# Gateway.net
KiCad netlist of a schematic drawn in Altium Designer
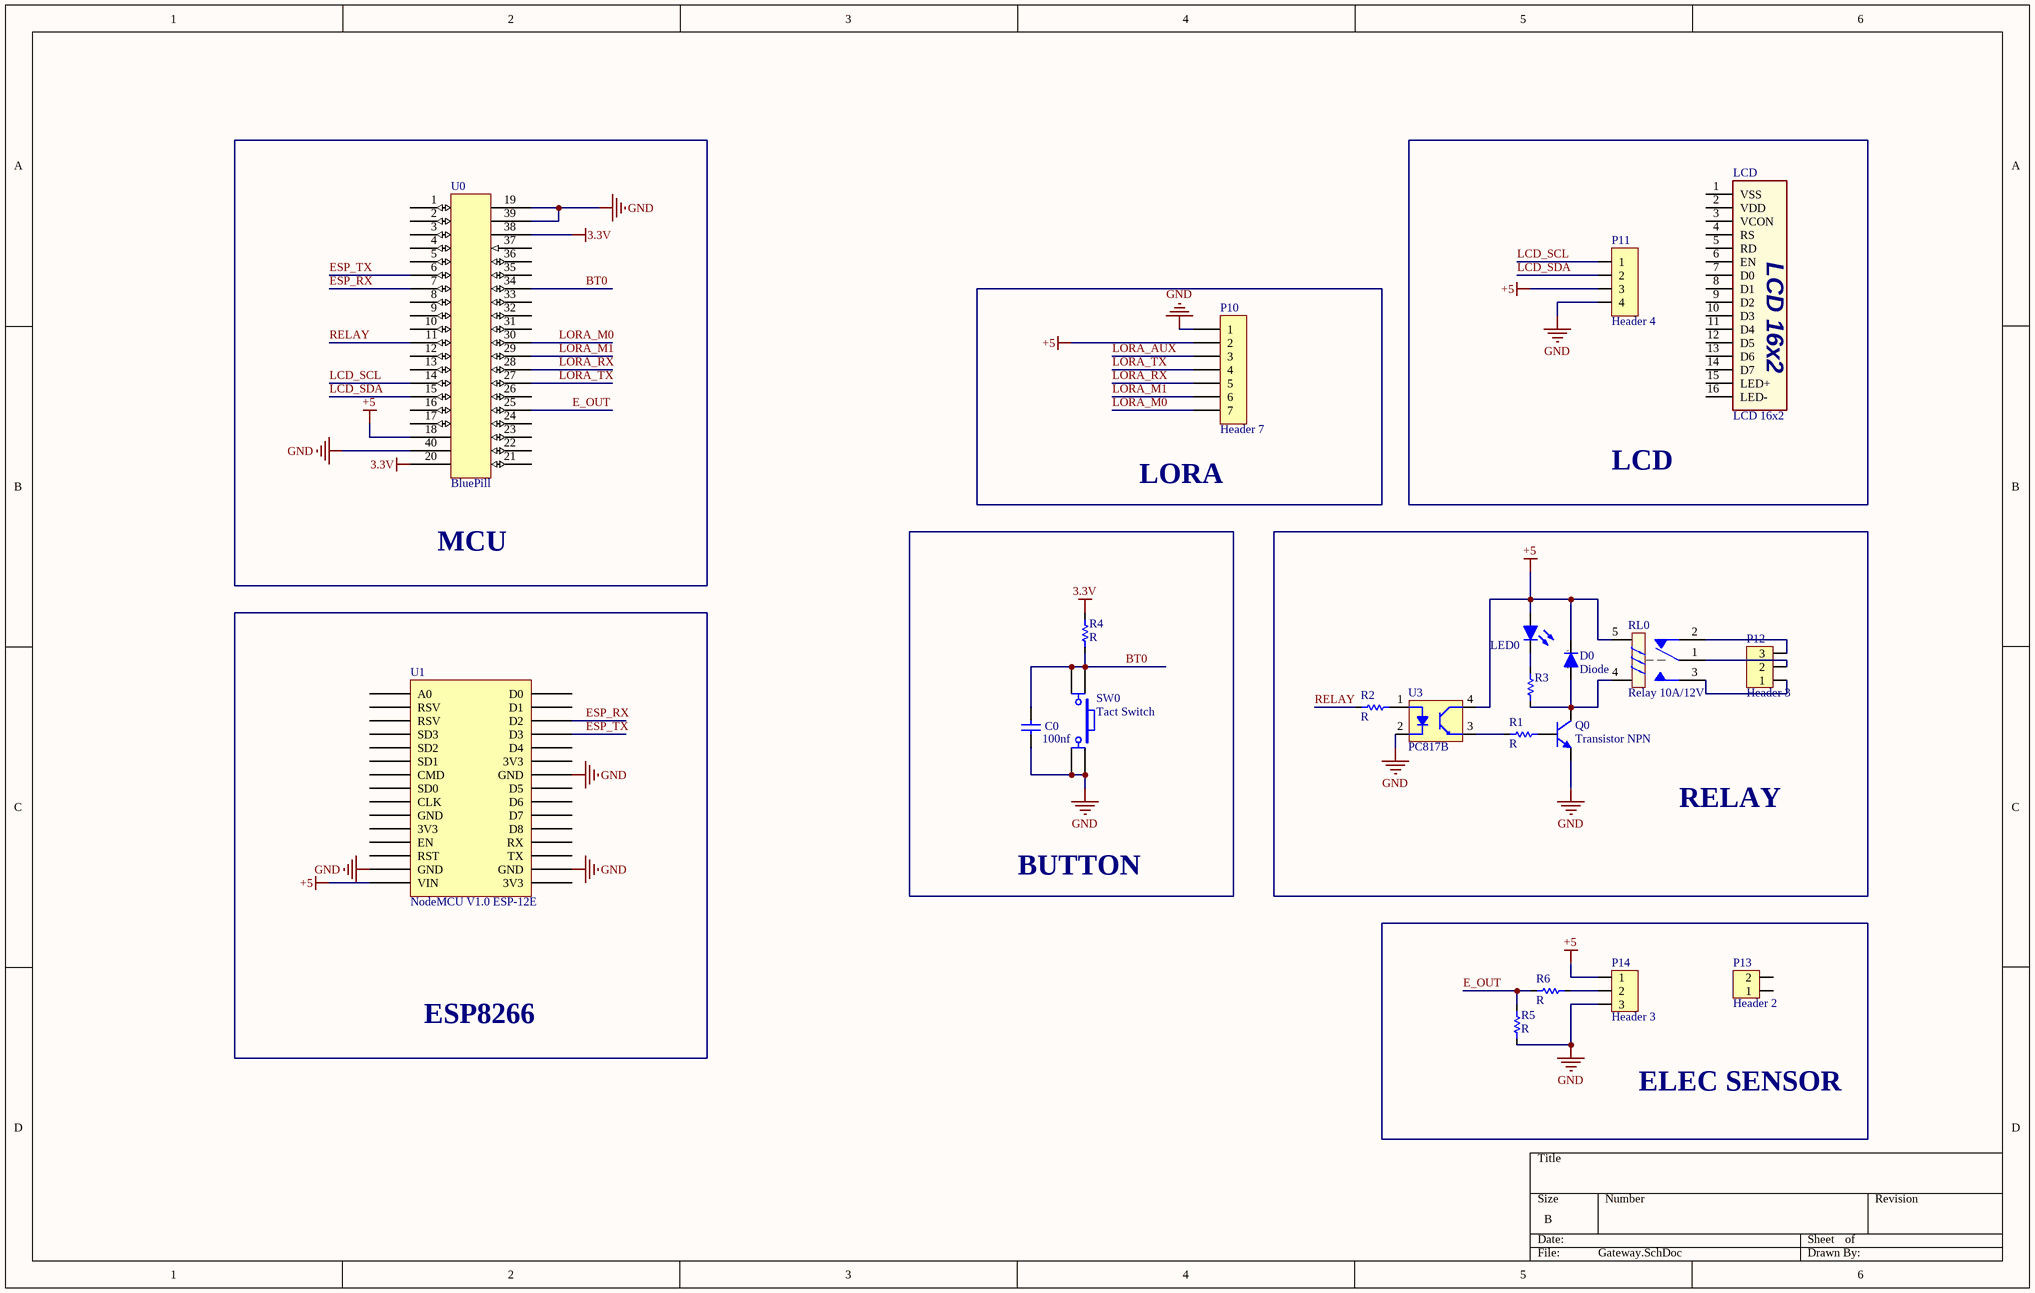
[diagram p0: Gateway.SchDoc]

(export (version "E")
  (design (tool "Eeschema 10.0.6"))
  (components
    (comp (ref "C0")
      (value "100nf")
      (footprint "C 0805 (2012)")
      (description "Capacitor non-pol")
      (libsource (lib "BKIT4U_LIB_NEW") (part "Capacitor NP"))
    )
    (comp (ref "D0")
      (value "Diode")
      (footprint "SOD-80")
      (description "Default Diode")
      (fields (field (name "PUBLISHER") "Altium Limited"))
      (libsource (lib "BKIT4U_LIB_NEW") (part "Diode"))
    )
    (comp (ref "LCD")
      (value "LCD 16x2")
      (footprint "LCD 16x2")
      (description "Character LCD 16x2")
      (libsource (lib "BKIT4U_LIB_NEW") (part "LCD 16x2"))
    )
    (comp (ref "LED0")
      (value "Led")
      (footprint "LED 3MM")
      (description "Typical LED")
      (libsource (lib "BKIT4U_LIB_NEW") (part "Led"))
    )
    (comp (ref "P10")
      (value "Header 7")
      (footprint "Header 7")
      (description "Header, 7-Pin")
      (fields (field (name "PUBLISHER") "Altium Limited"))
      (libsource (lib "BKIT4U_LIB_NEW") (part "Header 7"))
    )
    (comp (ref "P11")
      (value "Header 4")
      (footprint "XH2.54-4P-RA")
      (description "Header, 4-Pin")
      (libsource (lib "BKIT4U_LIB_NEW") (part "Header 4"))
    )
    (comp (ref "P12")
      (value "Header 3")
      (footprint "SH152-5.08-3P")
      (description "Header, 3-Pin")
      (libsource (lib "") (part "Header 3_1"))
    )
    (comp (ref "P13")
      (value "Header 2")
      (footprint "HDR Domino 2 - 5MM")
      (description "Header, 2-Pin")
      (fields (field (name "PUBLISHER") "Altium Limited"))
      (libsource (lib "BKIT4U_LIB_NEW") (part "Header 2"))
    )
    (comp (ref "P14")
      (value "Header 3")
      (footprint "Header 3")
      (description "Header, 3-Pin")
      (libsource (lib "BKIT4U_LIB_NEW") (part "Header 3"))
    )
    (comp (ref "Q0")
      (value "Transistor NPN")
      (footprint "SOT-23")
      (description "NPN Bipolar Transistor")
      (libsource (lib "BKIT4U_LIB_NEW") (part "Transistor NPN"))
    )
    (comp (ref "R1")
      (value "R")
      (footprint "R 0805 (2012)")
      (description "Resistor")
      (fields (field (name "PUBLISHER") "Altium Limited"))
      (libsource (lib "BKIT4U_LIB_NEW") (part "Resistor"))
    )
    (comp (ref "R2")
      (value "R")
      (footprint "R 0805 (2012)")
      (description "Resistor")
      (fields (field (name "PUBLISHER") "Altium Limited"))
      (libsource (lib "BKIT4U_LIB_NEW") (part "Resistor"))
    )
    (comp (ref "R3")
      (value "R0")
      (footprint "R 0805 (2012)")
      (description "Resistor")
      (fields (field (name "PUBLISHER") "Altium Limited"))
      (libsource (lib "BKIT4U_LIB_NEW") (part "Resistor"))
    )
    (comp (ref "R4")
      (value "R")
      (footprint "R 0805 (2012)")
      (description "Resistor")
      (fields (field (name "PUBLISHER") "Altium Limited"))
      (libsource (lib "BKIT4U_LIB_NEW") (part "Resistor"))
    )
    (comp (ref "R5")
      (value "R")
      (footprint "R 0805 (2012)")
      (description "Resistor")
      (fields (field (name "PUBLISHER") "Altium Limited"))
      (libsource (lib "BKIT4U_LIB_NEW") (part "Resistor"))
    )
    (comp (ref "R6")
      (value "R")
      (footprint "R 0805 (2012)")
      (description "Resistor")
      (fields (field (name "PUBLISHER") "Altium Limited"))
      (libsource (lib "BKIT4U_LIB_NEW") (part "Resistor"))
    )
    (comp (ref "RL0")
      (value "Relay 10A/12V")
      (footprint "RL_SPDT_10A")
      (description "Relay SPDT,10A - 12VDC 5 Pin")
      (libsource (lib "BKIT4U_LIB_NEW") (part "Relay 1"))
    )
    (comp (ref "SW0")
      (value "Tact Switch")
      (footprint "SW/4/DIP/SMALL")
      (description "Tact switch 4 pin")
      (libsource (lib "BKIT4U_LIB_NEW") (part "SW SPST-4"))
    )
    (comp (ref "U0")
      (value "BluePill")
      (footprint "Footprints:YAAJ_BluePill_1")
      (libsource (lib "BluePill") (part "BluePill"))
    )
    (comp (ref "U1")
      (value "NodeMCU V1.0 ESP-12E")
      (footprint "NodeMCU V1.0 ESP-12E")
      (description "NodeMCU V1.0 ESP8266 (ESP-12E)")
      (libsource (lib "nodemcu") (part "NodeMCU V1.0 ESP-12E"))
    )
    (comp (ref "U3")
      (value "PC817B")
      (footprint "SOIC-4-GULLWING")
      (libsource (lib "BKIT4U_LIB_NEW") (part "Opto PC817B"))
    )
  )
  (nets
    (net (code "1") (name "+5") (class "Default")
      (node (ref "D0") (pin "1") (pinfunction "Cathode_1") (pintype "passive"))
      (node (ref "LED0") (pin "2") (pinfunction "A_2") (pintype "passive"))
      (node (ref "P10") (pin "2") (pinfunction "2_2") (pintype "passive"))
      (node (ref "P11") (pin "3") (pinfunction "3_3") (pintype "passive"))
      (node (ref "P14") (pin "1") (pinfunction "1_1") (pintype "passive"))
      (node (ref "RL0") (pin "5") (pinfunction "5_5") (pintype "passive"))
      (node (ref "U0") (pin "18") (pintype "power_in"))
      (node (ref "U1") (pin "VIN") (pinfunction "VIN_VIN") (pintype "passive"))
      (node (ref "U3") (pin "4") (pinfunction "C_4") (pintype "passive"))
    )
    (net (code "2") (name "/BT0") (class "Default")
      (node (ref "C0") (pin "1") (pinfunction "1_1") (pintype "passive"))
      (node (ref "R4") (pin "2") (pinfunction "2_2") (pintype "passive"))
      (node (ref "SW0") (pin "1") (pinfunction "1_1") (pintype "passive"))
      (node (ref "SW0") (pin "4") (pinfunction "2_4") (pintype "passive"))
      (node (ref "U0") (pin "34") (pintype "bidirectional"))
    )
    (net (code "3") (name "/ESP_RX") (class "Default")
      (node (ref "U0") (pin "7") (pintype "bidirectional"))
      (node (ref "U1") (pin "D2") (pinfunction "D2_D2") (pintype "passive"))
    )
    (net (code "4") (name "/ESP_TX") (class "Default")
      (node (ref "U0") (pin "6") (pintype "bidirectional"))
      (node (ref "U1") (pin "D3") (pinfunction "D3_D3") (pintype "passive"))
    )
    (net (code "5") (name "/E_OUT") (class "Default")
      (node (ref "R5") (pin "1") (pinfunction "1_1") (pintype "passive"))
      (node (ref "R6") (pin "2") (pinfunction "2_2") (pintype "passive"))
      (node (ref "U0") (pin "25") (pintype "bidirectional"))
    )
    (net (code "6") (name "/LCD_SCL") (class "Default")
      (node (ref "P11") (pin "1") (pinfunction "1_1") (pintype "passive"))
      (node (ref "U0") (pin "14") (pintype "bidirectional"))
    )
    (net (code "7") (name "/LCD_SDA") (class "Default")
      (node (ref "P11") (pin "2") (pinfunction "2_2") (pintype "passive"))
      (node (ref "U0") (pin "15") (pintype "bidirectional"))
    )
    (net (code "8") (name "/LORA_AUX") (class "Default")
      (node (ref "P10") (pin "3") (pinfunction "3_3") (pintype "passive"))
    )
    (net (code "9") (name "/LORA_M0") (class "Default")
      (node (ref "P10") (pin "7") (pinfunction "7_7") (pintype "passive"))
      (node (ref "U0") (pin "30") (pintype "bidirectional"))
    )
    (net (code "10") (name "/LORA_M1") (class "Default")
      (node (ref "P10") (pin "6") (pinfunction "6_6") (pintype "passive"))
      (node (ref "U0") (pin "29") (pintype "bidirectional"))
    )
    (net (code "11") (name "/LORA_RX") (class "Default")
      (node (ref "P10") (pin "5") (pinfunction "5_5") (pintype "passive"))
      (node (ref "U0") (pin "28") (pintype "bidirectional"))
    )
    (net (code "12") (name "/LORA_TX") (class "Default")
      (node (ref "P10") (pin "4") (pinfunction "4_4") (pintype "passive"))
      (node (ref "U0") (pin "27") (pintype "bidirectional"))
    )
    (net (code "13") (name "/RELAY") (class "Default")
      (node (ref "R2") (pin "2") (pinfunction "2_2") (pintype "passive"))
      (node (ref "U0") (pin "11") (pintype "bidirectional"))
    )
    (net (code "14") (name "3.3V") (class "Default")
      (node (ref "R4") (pin "1") (pinfunction "1_1") (pintype "passive"))
      (node (ref "U0") (pin "20") (pintype "power_in"))
      (node (ref "U0") (pin "38") (pintype "power_in"))
    )
    (net (code "15") (name "GND") (class "Default")
      (node (ref "C0") (pin "2") (pinfunction "2_2") (pintype "passive"))
      (node (ref "P10") (pin "1") (pinfunction "1_1") (pintype "passive"))
      (node (ref "P11") (pin "4") (pinfunction "4_4") (pintype "passive"))
      (node (ref "P14") (pin "3") (pinfunction "3_3") (pintype "passive"))
      (node (ref "Q0") (pin "2") (pinfunction "E_2") (pintype "passive"))
      (node (ref "R5") (pin "2") (pinfunction "2_2") (pintype "passive"))
      (node (ref "SW0") (pin "2") (pinfunction "2_2") (pintype "passive"))
      (node (ref "SW0") (pin "3") (pinfunction "1_3") (pintype "passive"))
      (node (ref "U0") (pin "19") (pintype "power_in"))
      (node (ref "U0") (pin "39") (pintype "power_in"))
      (node (ref "U0") (pin "40") (pintype "power_in"))
      (node (ref "U1") (pin "GND") (pinfunction "GND_GND") (pintype "passive"))
      (node (ref "U3") (pin "2") (pinfunction "K_2") (pintype "passive"))
    )
    (net (code "16") (name "Net-(D0-Anode)") (class "Default")
      (node (ref "D0") (pin "2") (pinfunction "Anode_2") (pintype "passive"))
      (node (ref "Q0") (pin "3") (pinfunction "C_3") (pintype "passive"))
      (node (ref "R3") (pin "1") (pinfunction "1_1") (pintype "passive"))
      (node (ref "RL0") (pin "4") (pinfunction "4_4") (pintype "passive"))
    )
    (net (code "17") (name "Net-(LED0-K)") (class "Default")
      (node (ref "LED0") (pin "1") (pinfunction "K_1") (pintype "passive"))
      (node (ref "R3") (pin "2") (pinfunction "2_2") (pintype "passive"))
    )
    (net (code "18") (name "Net-(P12-Pad1)") (class "Default")
      (node (ref "P12") (pin "1") (pinfunction "1_1") (pintype "passive"))
      (node (ref "RL0") (pin "3") (pinfunction "3_3") (pintype "passive"))
    )
    (net (code "19") (name "Net-(P12-Pad2)") (class "Default")
      (node (ref "P12") (pin "2") (pinfunction "2_2") (pintype "passive"))
      (node (ref "RL0") (pin "1") (pinfunction "1_1") (pintype "passive"))
    )
    (net (code "20") (name "Net-(P12-Pad3)") (class "Default")
      (node (ref "P12") (pin "3") (pinfunction "3_3") (pintype "passive"))
      (node (ref "RL0") (pin "2") (pinfunction "2_2") (pintype "passive"))
    )
    (net (code "21") (name "Net-(P14-Pad2)") (class "Default")
      (node (ref "P14") (pin "2") (pinfunction "2_2") (pintype "passive"))
      (node (ref "R6") (pin "1") (pinfunction "1_1") (pintype "passive"))
    )
    (net (code "22") (name "Net-(Q0-B)") (class "Default")
      (node (ref "Q0") (pin "1") (pinfunction "B_1") (pintype "passive"))
      (node (ref "R1") (pin "1") (pinfunction "1_1") (pintype "passive"))
    )
    (net (code "23") (name "Net-(U3-A)") (class "Default")
      (node (ref "R2") (pin "1") (pinfunction "1_1") (pintype "passive"))
      (node (ref "U3") (pin "1") (pinfunction "A_1") (pintype "passive"))
    )
    (net (code "24") (name "Net-(U3-E)") (class "Default")
      (node (ref "R1") (pin "2") (pinfunction "2_2") (pintype "passive"))
      (node (ref "U3") (pin "3") (pinfunction "E_3") (pintype "passive"))
    )
    (net (code "25") (name "unconnected-(LCD-D0-Pad7)") (class "Default")
      (node (ref "LCD") (pin "7") (pinfunction "D0_7") (pintype "passive"))
    )
    (net (code "26") (name "unconnected-(LCD-D1-Pad8)") (class "Default")
      (node (ref "LCD") (pin "8") (pinfunction "D1_8") (pintype "passive"))
    )
    (net (code "27") (name "unconnected-(LCD-D2-Pad9)") (class "Default")
      (node (ref "LCD") (pin "9") (pinfunction "D2_9") (pintype "passive"))
    )
    (net (code "28") (name "unconnected-(LCD-D3-Pad10)") (class "Default")
      (node (ref "LCD") (pin "10") (pinfunction "D3_10") (pintype "passive"))
    )
    (net (code "29") (name "unconnected-(LCD-D4-Pad11)") (class "Default")
      (node (ref "LCD") (pin "11") (pinfunction "D4_11") (pintype "passive"))
    )
    (net (code "30") (name "unconnected-(LCD-D5-Pad12)") (class "Default")
      (node (ref "LCD") (pin "12") (pinfunction "D5_12") (pintype "passive"))
    )
    (net (code "31") (name "unconnected-(LCD-D6-Pad13)") (class "Default")
      (node (ref "LCD") (pin "13") (pinfunction "D6_13") (pintype "passive"))
    )
    (net (code "32") (name "unconnected-(LCD-D7-Pad14)") (class "Default")
      (node (ref "LCD") (pin "14") (pinfunction "D7_14") (pintype "passive"))
    )
    (net (code "33") (name "unconnected-(LCD-EN-Pad6)") (class "Default")
      (node (ref "LCD") (pin "6") (pinfunction "EN_6") (pintype "passive"))
    )
    (net (code "34") (name "unconnected-(LCD-LED+-Pad15)") (class "Default")
      (node (ref "LCD") (pin "15") (pinfunction "LED+_15") (pintype "passive"))
    )
    (net (code "35") (name "unconnected-(LCD-LED--Pad16)") (class "Default")
      (node (ref "LCD") (pin "16") (pinfunction "LED-_16") (pintype "passive"))
    )
    (net (code "36") (name "unconnected-(LCD-RD-Pad5)") (class "Default")
      (node (ref "LCD") (pin "5") (pinfunction "RD_5") (pintype "passive"))
    )
    (net (code "37") (name "unconnected-(LCD-RS-Pad4)") (class "Default")
      (node (ref "LCD") (pin "4") (pinfunction "RS_4") (pintype "passive"))
    )
    (net (code "38") (name "unconnected-(LCD-VCON-Pad3)") (class "Default")
      (node (ref "LCD") (pin "3") (pinfunction "VCON_3") (pintype "passive"))
    )
    (net (code "39") (name "unconnected-(LCD-VDD-Pad2)") (class "Default")
      (node (ref "LCD") (pin "2") (pinfunction "VDD_2") (pintype "passive"))
    )
    (net (code "40") (name "unconnected-(LCD-VSS-Pad1)") (class "Default")
      (node (ref "LCD") (pin "1") (pinfunction "VSS_1") (pintype "passive"))
    )
    (net (code "41") (name "unconnected-(P13-Pad1)") (class "Default")
      (node (ref "P13") (pin "1") (pinfunction "1_1") (pintype "passive"))
    )
    (net (code "42") (name "unconnected-(P13-Pad2)") (class "Default")
      (node (ref "P13") (pin "2") (pinfunction "2_2") (pintype "passive"))
    )
    (net (code "43") (name "unconnected-(U0-Pad1)") (class "Default")
      (node (ref "U0") (pin "1") (pintype "bidirectional"))
    )
    (net (code "44") (name "unconnected-(U0-Pad2)") (class "Default")
      (node (ref "U0") (pin "2") (pintype "bidirectional"))
    )
    (net (code "45") (name "unconnected-(U0-Pad3)") (class "Default")
      (node (ref "U0") (pin "3") (pintype "bidirectional"))
    )
    (net (code "46") (name "unconnected-(U0-Pad4)") (class "Default")
      (node (ref "U0") (pin "4") (pintype "bidirectional"))
    )
    (net (code "47") (name "unconnected-(U0-Pad5)") (class "Default")
      (node (ref "U0") (pin "5") (pintype "bidirectional"))
    )
    (net (code "48") (name "unconnected-(U0-Pad8)") (class "Default")
      (node (ref "U0") (pin "8") (pintype "bidirectional"))
    )
    (net (code "49") (name "unconnected-(U0-Pad9)") (class "Default")
      (node (ref "U0") (pin "9") (pintype "bidirectional"))
    )
    (net (code "50") (name "unconnected-(U0-Pad10)") (class "Default")
      (node (ref "U0") (pin "10") (pintype "bidirectional"))
    )
    (net (code "51") (name "unconnected-(U0-Pad12)") (class "Default")
      (node (ref "U0") (pin "12") (pintype "bidirectional"))
    )
    (net (code "52") (name "unconnected-(U0-Pad13)") (class "Default")
      (node (ref "U0") (pin "13") (pintype "bidirectional"))
    )
    (net (code "53") (name "unconnected-(U0-Pad16)") (class "Default")
      (node (ref "U0") (pin "16") (pintype "bidirectional"))
    )
    (net (code "54") (name "unconnected-(U0-Pad17)") (class "Default")
      (node (ref "U0") (pin "17") (pintype "bidirectional"))
    )
    (net (code "55") (name "unconnected-(U0-Pad21)") (class "Default")
      (node (ref "U0") (pin "21") (pintype "bidirectional"))
    )
    (net (code "56") (name "unconnected-(U0-Pad22)") (class "Default")
      (node (ref "U0") (pin "22") (pintype "bidirectional"))
    )
    (net (code "57") (name "unconnected-(U0-Pad23)") (class "Default")
      (node (ref "U0") (pin "23") (pintype "bidirectional"))
    )
    (net (code "58") (name "unconnected-(U0-Pad24)") (class "Default")
      (node (ref "U0") (pin "24") (pintype "bidirectional"))
    )
    (net (code "59") (name "unconnected-(U0-Pad26)") (class "Default")
      (node (ref "U0") (pin "26") (pintype "bidirectional"))
    )
    (net (code "60") (name "unconnected-(U0-Pad31)") (class "Default")
      (node (ref "U0") (pin "31") (pintype "bidirectional"))
    )
    (net (code "61") (name "unconnected-(U0-Pad32)") (class "Default")
      (node (ref "U0") (pin "32") (pintype "bidirectional"))
    )
    (net (code "62") (name "unconnected-(U0-Pad33)") (class "Default")
      (node (ref "U0") (pin "33") (pintype "bidirectional"))
    )
    (net (code "63") (name "unconnected-(U0-Pad35)") (class "Default")
      (node (ref "U0") (pin "35") (pintype "bidirectional"))
    )
    (net (code "64") (name "unconnected-(U0-Pad36)") (class "Default")
      (node (ref "U0") (pin "36") (pintype "bidirectional"))
    )
    (net (code "65") (name "unconnected-(U0-Pad37)") (class "Default")
      (node (ref "U0") (pin "37") (pintype "input"))
    )
    (net (code "66") (name "unconnected-(U1-Pad3V3)") (class "Default")
      (node (ref "U1") (pin "3V3") (pinfunction "3V3_3V3") (pintype "passive"))
    )
    (net (code "67") (name "unconnected-(U1-Pad3V3)_1") (class "Default")
      (node (ref "U1") (pin "3V3") (pinfunction "3V3_3V3") (pintype "passive"))
    )
    (net (code "68") (name "unconnected-(U1-Pad3V3)_2") (class "Default")
      (node (ref "U1") (pin "3V3") (pinfunction "3V3_3V3") (pintype "passive"))
    )
    (net (code "69") (name "unconnected-(U1-PadA0)") (class "Default")
      (node (ref "U1") (pin "A0") (pinfunction "A0_A0") (pintype "passive"))
    )
    (net (code "70") (name "unconnected-(U1-PadCLK)") (class "Default")
      (node (ref "U1") (pin "CLK") (pinfunction "CLK_CLK") (pintype "passive"))
    )
    (net (code "71") (name "unconnected-(U1-PadCMD)") (class "Default")
      (node (ref "U1") (pin "CMD") (pinfunction "CMD_CMD") (pintype "passive"))
    )
    (net (code "72") (name "unconnected-(U1-PadD0)") (class "Default")
      (node (ref "U1") (pin "D0") (pinfunction "D0_D0") (pintype "passive"))
    )
    (net (code "73") (name "unconnected-(U1-PadD1)") (class "Default")
      (node (ref "U1") (pin "D1") (pinfunction "D1_D1") (pintype "passive"))
    )
    (net (code "74") (name "unconnected-(U1-PadD4)") (class "Default")
      (node (ref "U1") (pin "D4") (pinfunction "D4_D4") (pintype "passive"))
    )
    (net (code "75") (name "unconnected-(U1-PadD5)") (class "Default")
      (node (ref "U1") (pin "D5") (pinfunction "D5_D5") (pintype "passive"))
    )
    (net (code "76") (name "unconnected-(U1-PadD6)") (class "Default")
      (node (ref "U1") (pin "D6") (pinfunction "D6_D6") (pintype "passive"))
    )
    (net (code "77") (name "unconnected-(U1-PadD7)") (class "Default")
      (node (ref "U1") (pin "D7") (pinfunction "D7_D7") (pintype "passive"))
    )
    (net (code "78") (name "unconnected-(U1-PadD8)") (class "Default")
      (node (ref "U1") (pin "D8") (pinfunction "D8_D8") (pintype "passive"))
    )
    (net (code "79") (name "unconnected-(U1-PadEN)") (class "Default")
      (node (ref "U1") (pin "EN") (pinfunction "EN_EN") (pintype "passive"))
    )
    (net (code "80") (name "unconnected-(U1-PadGND)") (class "Default")
      (node (ref "U1") (pin "GND") (pinfunction "GND_GND") (pintype "passive"))
    )
    (net (code "81") (name "unconnected-(U1-PadRST)") (class "Default")
      (node (ref "U1") (pin "RST") (pinfunction "RST_RST") (pintype "passive"))
    )
    (net (code "82") (name "unconnected-(U1-PadRSV)") (class "Default")
      (node (ref "U1") (pin "RSV") (pinfunction "RSV_RSV") (pintype "passive"))
    )
    (net (code "83") (name "unconnected-(U1-PadRSV)_1") (class "Default")
      (node (ref "U1") (pin "RSV") (pinfunction "RSV_RSV") (pintype "passive"))
    )
    (net (code "84") (name "unconnected-(U1-PadRX)") (class "Default")
      (node (ref "U1") (pin "RX") (pinfunction "RX_RX") (pintype "passive"))
    )
    (net (code "85") (name "unconnected-(U1-PadSD0)") (class "Default")
      (node (ref "U1") (pin "SD0") (pinfunction "SD0_SD0") (pintype "passive"))
    )
    (net (code "86") (name "unconnected-(U1-PadSD1)") (class "Default")
      (node (ref "U1") (pin "SD1") (pinfunction "SD1_SD1") (pintype "passive"))
    )
    (net (code "87") (name "unconnected-(U1-PadSD2)") (class "Default")
      (node (ref "U1") (pin "SD2") (pinfunction "SD2_SD2") (pintype "passive"))
    )
    (net (code "88") (name "unconnected-(U1-PadSD3)") (class "Default")
      (node (ref "U1") (pin "SD3") (pinfunction "SD3_SD3") (pintype "passive"))
    )
    (net (code "89") (name "unconnected-(U1-PadTX)") (class "Default")
      (node (ref "U1") (pin "TX") (pinfunction "TX_TX") (pintype "passive"))
    )
  )
)
